# Power_USB.net
KiCad netlist of a schematic drawn in Altium Designer
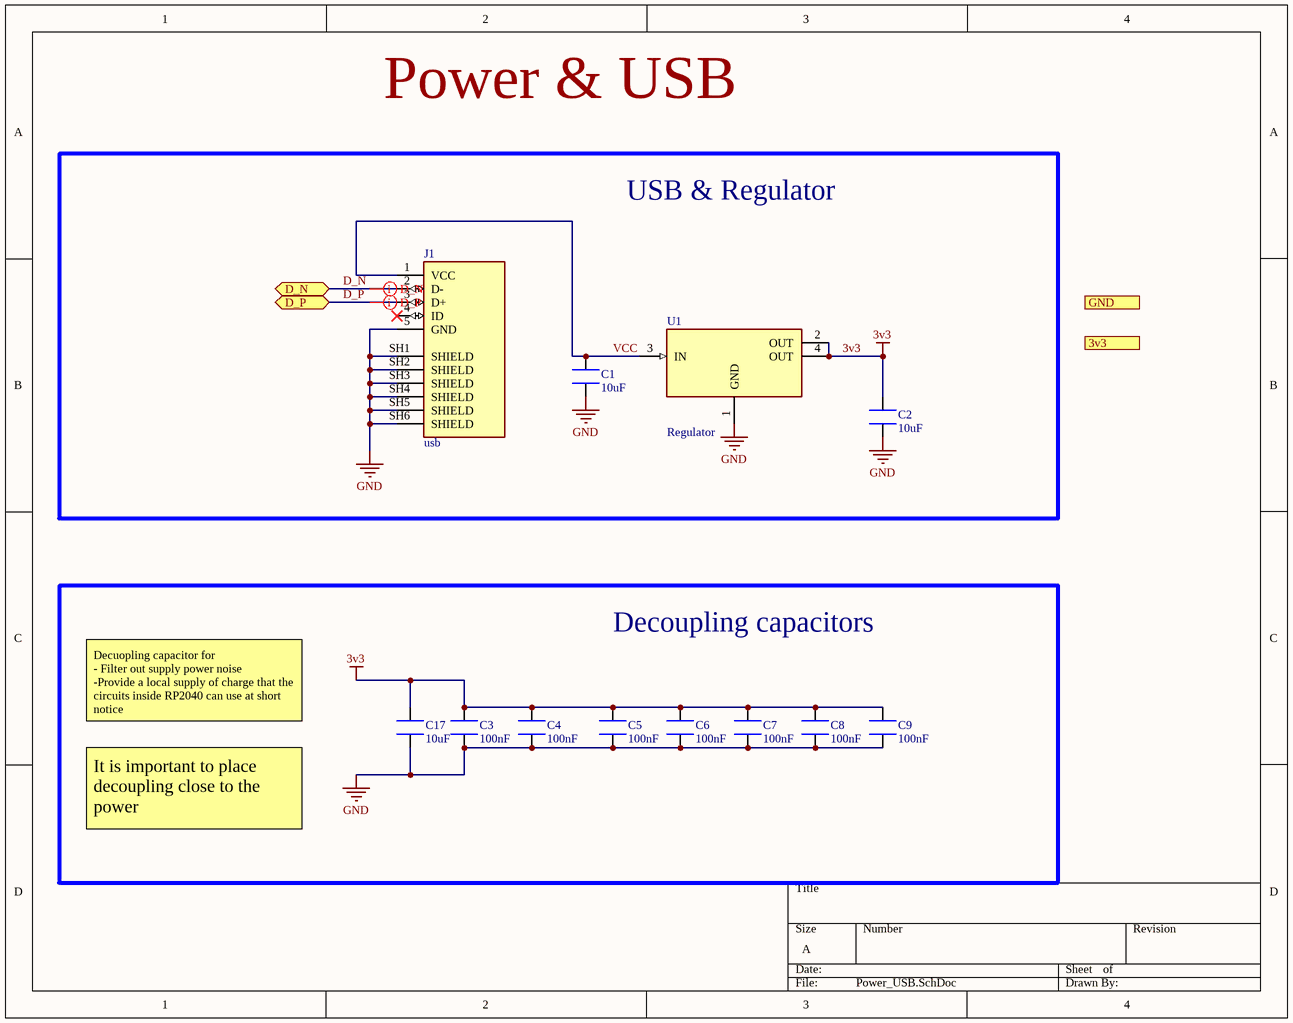
[diagram p0: Power_USB.SchDoc]

(export (version "E")
  (design (tool "Eeschema 10.0.6"))
  (components
    (comp (ref "C1")
      (value "10uF")
      (footprint "CL21A106KOQNNNG")
      (description "SMD ceramic capacitor 10µF, tolerance±10% 16V  X5R 0805 _2012 Metric")
      (fields
        (field (name "MF") "Samsung Electro-Mechanics")
        (field (name "DIGI-KEY_PART_NUMBER") "1276-6455-1-ND")
      )
      (libsource (lib "RP2040intLib") (part "CL21A106KOQNNNG"))
    )
    (comp (ref "C2")
      (value "10uF")
      (footprint "CL21A106KOQNNNG")
      (description "SMD ceramic capacitor 10µF, tolerance±10% 16V  X5R 0805 _2012 Metric")
      (fields
        (field (name "MF") "Samsung Electro-Mechanics")
        (field (name "DIGI-KEY_PART_NUMBER") "1276-6455-1-ND")
      )
      (libsource (lib "RP2040intLib") (part "CL21A106KOQNNNG"))
    )
    (comp (ref "C3")
      (value "100nF")
      (footprint "CL10B104KB8NNNC")
      (description "SMD ceramic capacitor 0.1µF, tolerance ±10% 50V 0603 _1608 Metric_")
      (fields (field (name "MP") "CL10B104KB8NNNC") (field (name "MF") "Samsung Electro-Mechanics"))
      (libsource (lib "RP2040intLib") (part "CL10B104KB8NNNC"))
    )
    (comp (ref "C4")
      (value "100nF")
      (footprint "CL10B104KB8NNNC")
      (description "SMD ceramic capacitor 0.1µF, tolerance ±10% 50V 0603 _1608 Metric_")
      (fields (field (name "MP") "CL10B104KB8NNNC") (field (name "MF") "Samsung Electro-Mechanics"))
      (libsource (lib "RP2040intLib") (part "CL10B104KB8NNNC"))
    )
    (comp (ref "C5")
      (value "100nF")
      (footprint "CL10B104KB8NNNC")
      (description "SMD ceramic capacitor 0.1µF, tolerance ±10% 50V 0603 _1608 Metric_")
      (fields (field (name "MP") "CL10B104KB8NNNC") (field (name "MF") "Samsung Electro-Mechanics"))
      (libsource (lib "RP2040intLib") (part "CL10B104KB8NNNC"))
    )
    (comp (ref "C6")
      (value "100nF")
      (footprint "CL10B104KB8NNNC")
      (description "SMD ceramic capacitor 0.1µF, tolerance ±10% 50V 0603 _1608 Metric_")
      (fields (field (name "MP") "CL10B104KB8NNNC") (field (name "MF") "Samsung Electro-Mechanics"))
      (libsource (lib "RP2040intLib") (part "CL10B104KB8NNNC"))
    )
    (comp (ref "C7")
      (value "100nF")
      (footprint "CL10B104KB8NNNC")
      (description "SMD ceramic capacitor 0.1µF, tolerance ±10% 50V 0603 _1608 Metric_")
      (fields (field (name "MP") "CL10B104KB8NNNC") (field (name "MF") "Samsung Electro-Mechanics"))
      (libsource (lib "RP2040intLib") (part "CL10B104KB8NNNC"))
    )
    (comp (ref "C8")
      (value "100nF")
      (footprint "CL10B104KB8NNNC")
      (description "SMD ceramic capacitor 0.1µF, tolerance ±10% 50V 0603 _1608 Metric_")
      (fields (field (name "MP") "CL10B104KB8NNNC") (field (name "MF") "Samsung Electro-Mechanics"))
      (libsource (lib "RP2040intLib") (part "CL10B104KB8NNNC"))
    )
    (comp (ref "C9")
      (value "100nF")
      (footprint "CL10B104KB8NNNC")
      (description "SMD ceramic capacitor 0.1µF, tolerance ±10% 50V 0603 _1608 Metric_")
      (fields (field (name "MP") "CL10B104KB8NNNC") (field (name "MF") "Samsung Electro-Mechanics"))
      (libsource (lib "RP2040intLib") (part "CL10B104KB8NNNC"))
    )
    (comp (ref "C17")
      (value "10uF")
      (footprint "CL21A106KOQNNNG")
      (description "SMD ceramic capacitor 10µF, tolerance±10% 16V  X5R 0805 _2012 Metric")
      (fields
        (field (name "MF") "Samsung Electro-Mechanics")
        (field (name "DIGI-KEY_PART_NUMBER") "1276-6455-1-ND")
      )
      (libsource (lib "RP2040intLib") (part "CL21A106KOQNNNG"))
    )
    (comp (ref "J1")
      (value "usb")
      (footprint "AMPHENOL_10118194-0001LF")
      (description "Micro USB, Input Output Connectors, B TYPE RECEPTACLE with flange")
      (fields (field (name "MF") "Amphenol ICC") (field (name "MP") "10118194-0001LF"))
      (libsource (lib "RP2040intLib") (part "10118194-0001LF"))
    )
    (comp (ref "U1")
      (value "Regulator")
      (footprint "SOT230P700X180-4N")
      (description "Linear Voltage Regulator IC 1 Output 1A SOT-223")
      (fields (field (name "MP") "NCP1117ST50T3G") (field (name "MF") "ON Semiconductor"))
      (libsource (lib "RP2040intLib") (part "NCP1117ST50T3G"))
    )
  )
  (nets
    (net (code "1") (name "/D_N") (class "Default")
      (node (ref "J1") (pin "2") (pinfunction "D-_2") (pintype "bidirectional"))
    )
    (net (code "2") (name "/D_P") (class "Default")
      (node (ref "J1") (pin "3") (pinfunction "D+_3") (pintype "bidirectional"))
    )
    (net (code "3") (name "/VCC") (class "Default")
      (node (ref "C1") (pin "2") (pinfunction "2_2") (pintype "passive"))
      (node (ref "J1") (pin "1") (pinfunction "VCC_1") (pintype "power_in"))
      (node (ref "U1") (pin "3") (pinfunction "IN_3") (pintype "input"))
    )
    (net (code "4") (name "3v3") (class "Default")
      (node (ref "C17") (pin "2") (pinfunction "2_2") (pintype "passive"))
      (node (ref "C2") (pin "2") (pinfunction "2_2") (pintype "passive"))
      (node (ref "C3") (pin "2") (pinfunction "2_2") (pintype "passive"))
      (node (ref "C4") (pin "2") (pinfunction "2_2") (pintype "passive"))
      (node (ref "C5") (pin "2") (pinfunction "2_2") (pintype "passive"))
      (node (ref "C6") (pin "2") (pinfunction "2_2") (pintype "passive"))
      (node (ref "C7") (pin "2") (pinfunction "2_2") (pintype "passive"))
      (node (ref "C8") (pin "2") (pinfunction "2_2") (pintype "passive"))
      (node (ref "C9") (pin "2") (pinfunction "2_2") (pintype "passive"))
      (node (ref "U1") (pin "2") (pinfunction "OUT_2") (pintype "power_in"))
      (node (ref "U1") (pin "4") (pinfunction "OUT_4") (pintype "power_in"))
    )
    (net (code "5") (name "GND") (class "Default")
      (node (ref "C1") (pin "1") (pinfunction "1_1") (pintype "passive"))
      (node (ref "C17") (pin "1") (pinfunction "1_1") (pintype "passive"))
      (node (ref "C2") (pin "1") (pinfunction "1_1") (pintype "passive"))
      (node (ref "C3") (pin "1") (pinfunction "1_1") (pintype "passive"))
      (node (ref "C4") (pin "1") (pinfunction "1_1") (pintype "passive"))
      (node (ref "C5") (pin "1") (pinfunction "1_1") (pintype "passive"))
      (node (ref "C6") (pin "1") (pinfunction "1_1") (pintype "passive"))
      (node (ref "C7") (pin "1") (pinfunction "1_1") (pintype "passive"))
      (node (ref "C8") (pin "1") (pinfunction "1_1") (pintype "passive"))
      (node (ref "C9") (pin "1") (pinfunction "1_1") (pintype "passive"))
      (node (ref "J1") (pin "5") (pinfunction "GND_5") (pintype "power_in"))
      (node (ref "J1") (pin "SH1") (pinfunction "SHIELD_SH1") (pintype "passive"))
      (node (ref "J1") (pin "SH2") (pinfunction "SHIELD_SH2") (pintype "passive"))
      (node (ref "J1") (pin "SH3") (pinfunction "SHIELD_SH3") (pintype "passive"))
      (node (ref "J1") (pin "SH4") (pinfunction "SHIELD_SH4") (pintype "passive"))
      (node (ref "J1") (pin "SH5") (pinfunction "SHIELD_SH5") (pintype "passive"))
      (node (ref "J1") (pin "SH6") (pinfunction "SHIELD_SH6") (pintype "passive"))
      (node (ref "U1") (pin "1") (pinfunction "GND_1") (pintype "power_in"))
    )
    (net (code "6") (name "unconnected-(J1-ID-Pad4)") (class "Default")
      (node (ref "J1") (pin "4") (pinfunction "ID_4") (pintype "bidirectional+no_connect"))
    )
  )
)
